# Layout.net
KiCad netlist of a schematic drawn in EAGLE
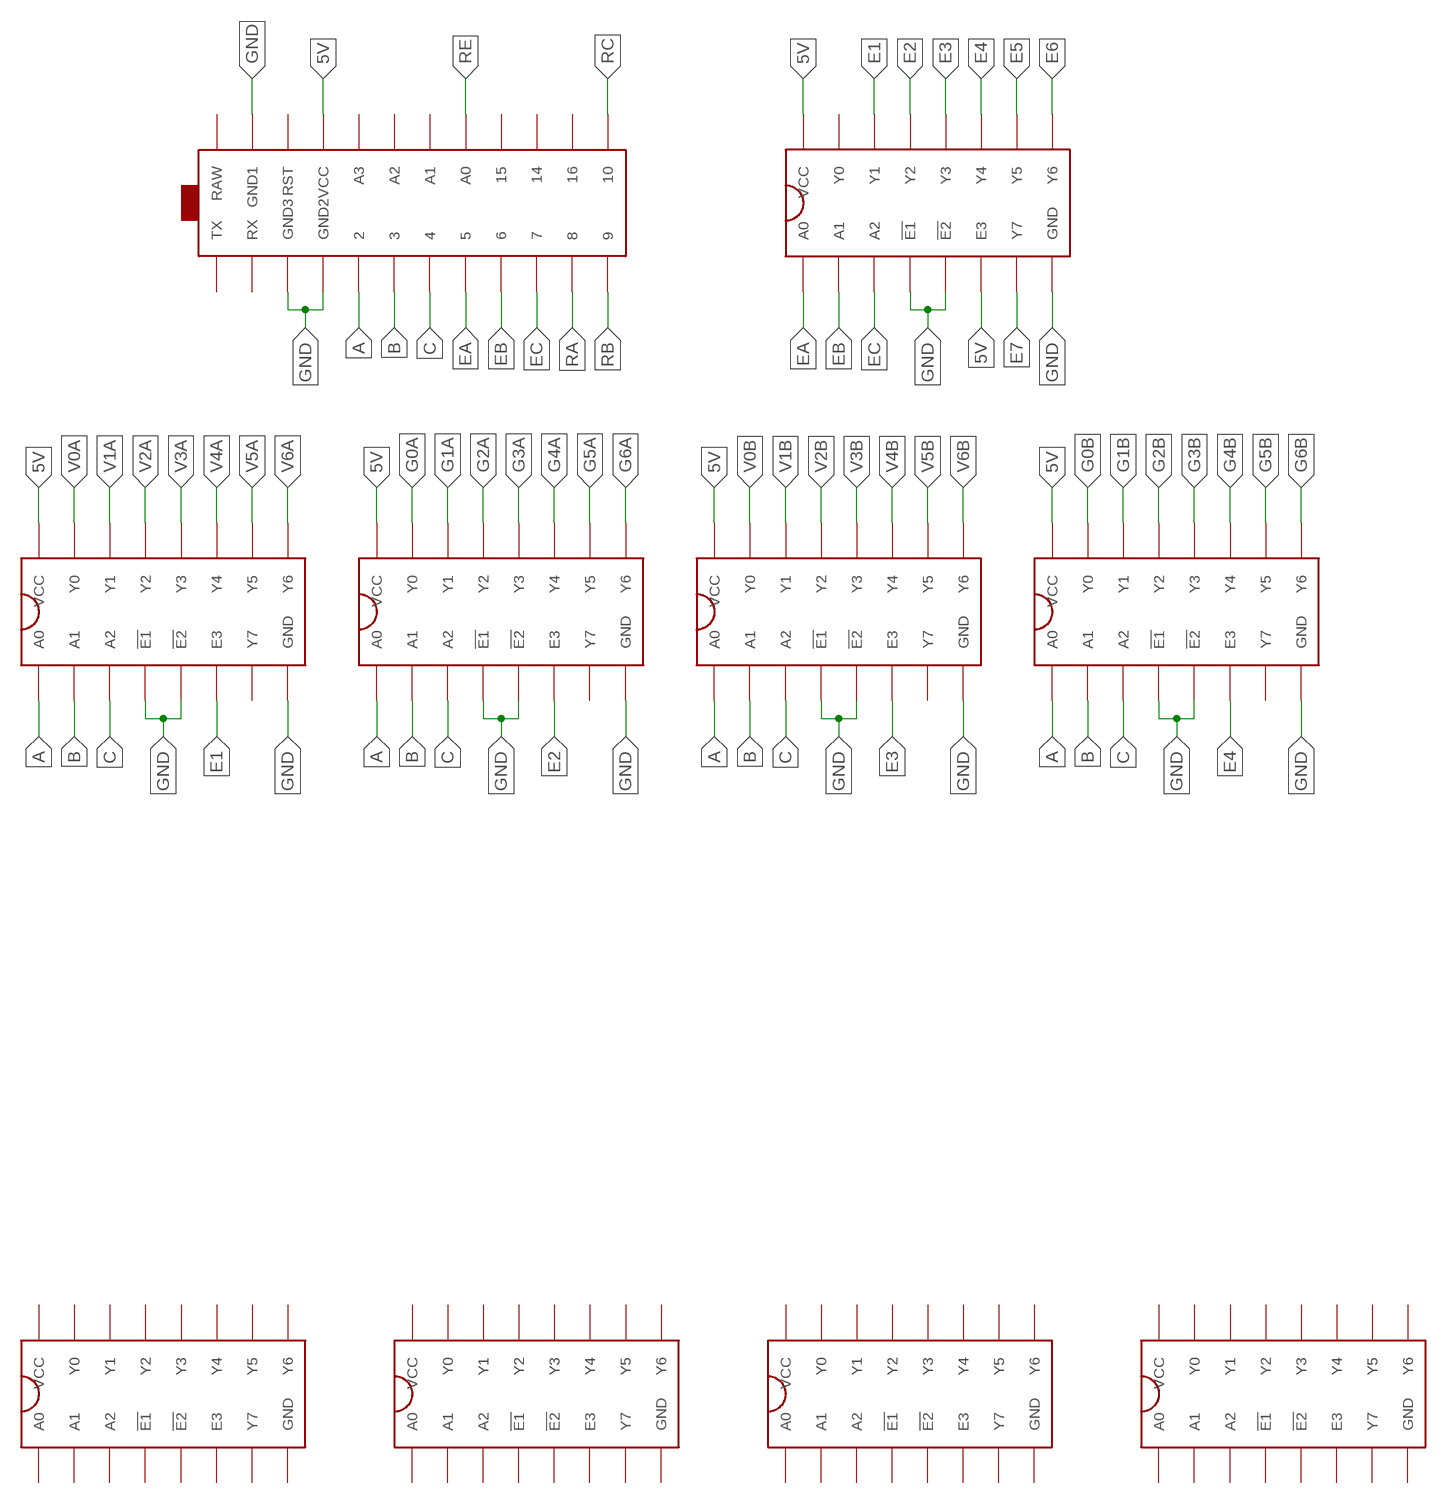
[diagram p0: schematic, sheet 1]

(export (version "E")
  (design (tool "Eeschema 10.0.6"))
  (components
    (comp (ref "U$1")
      (value "MCU")
      (footprint "eagle-import:MCU")
      (libsource (lib "eagle-import") (part "MCU"))
    )
    (comp (ref "U$2")
      (value "DEMUX")
      (footprint "eagle-import:DEMUX")
      (libsource (lib "eagle-import") (part "DEMUX"))
    )
    (comp (ref "U$3")
      (value "DEMUX")
      (footprint "eagle-import:DEMUX")
      (libsource (lib "eagle-import") (part "DEMUX"))
    )
    (comp (ref "U$4")
      (value "DEMUX")
      (footprint "eagle-import:DEMUX")
      (libsource (lib "eagle-import") (part "DEMUX"))
    )
    (comp (ref "U$5")
      (value "DEMUX")
      (footprint "eagle-import:DEMUX")
      (libsource (lib "eagle-import") (part "DEMUX"))
    )
    (comp (ref "U$6")
      (value "DEMUX")
      (footprint "eagle-import:DEMUX")
      (libsource (lib "eagle-import") (part "DEMUX"))
    )
    (comp (ref "U$7")
      (value "DEMUX")
      (footprint "eagle-import:DEMUX")
      (libsource (lib "eagle-import") (part "DEMUX"))
    )
    (comp (ref "U$8")
      (value "DEMUX")
      (footprint "eagle-import:DEMUX")
      (libsource (lib "eagle-import") (part "DEMUX"))
    )
    (comp (ref "U$9")
      (value "DEMUX")
      (footprint "eagle-import:DEMUX")
      (libsource (lib "eagle-import") (part "DEMUX"))
    )
    (comp (ref "U$10")
      (value "DEMUX")
      (footprint "eagle-import:DEMUX")
      (libsource (lib "eagle-import") (part "DEMUX"))
    )
  )
  (nets
    (net (code "1") (name "5V") (class "Default")
      (node (ref "U$1") (pin "P$24") (pinfunction "VCC_P$24") (pintype "bidirectional"))
      (node (ref "U$2") (pin "P$6") (pinfunction "E3_P$6") (pintype "bidirectional"))
      (node (ref "U$2") (pin "P$8") (pinfunction "VCC_P$8") (pintype "bidirectional"))
      (node (ref "U$3") (pin "P$8") (pinfunction "VCC_P$8") (pintype "bidirectional"))
      (node (ref "U$4") (pin "P$8") (pinfunction "VCC_P$8") (pintype "bidirectional"))
      (node (ref "U$5") (pin "P$8") (pinfunction "VCC_P$8") (pintype "bidirectional"))
      (node (ref "U$6") (pin "P$8") (pinfunction "VCC_P$8") (pintype "bidirectional"))
    )
    (net (code "2") (name "A") (class "Default")
      (node (ref "U$1") (pin "P$1") (pinfunction "2_P$1") (pintype "bidirectional"))
      (node (ref "U$3") (pin "P$3") (pinfunction "A0_P$3") (pintype "bidirectional"))
      (node (ref "U$4") (pin "P$3") (pinfunction "A0_P$3") (pintype "bidirectional"))
      (node (ref "U$5") (pin "P$3") (pinfunction "A0_P$3") (pintype "bidirectional"))
      (node (ref "U$6") (pin "P$3") (pinfunction "A0_P$3") (pintype "bidirectional"))
    )
    (net (code "3") (name "B") (class "Default")
      (node (ref "U$1") (pin "P$2") (pinfunction "3_P$2") (pintype "bidirectional"))
      (node (ref "U$3") (pin "P$4") (pinfunction "A1_P$4") (pintype "bidirectional"))
      (node (ref "U$4") (pin "P$4") (pinfunction "A1_P$4") (pintype "bidirectional"))
      (node (ref "U$5") (pin "P$4") (pinfunction "A1_P$4") (pintype "bidirectional"))
      (node (ref "U$6") (pin "P$4") (pinfunction "A1_P$4") (pintype "bidirectional"))
    )
    (net (code "4") (name "C") (class "Default")
      (node (ref "U$1") (pin "P$3") (pinfunction "4_P$3") (pintype "bidirectional"))
      (node (ref "U$3") (pin "P$5") (pinfunction "A2_P$5") (pintype "bidirectional"))
      (node (ref "U$4") (pin "P$5") (pinfunction "A2_P$5") (pintype "bidirectional"))
      (node (ref "U$5") (pin "P$5") (pinfunction "A2_P$5") (pintype "bidirectional"))
      (node (ref "U$6") (pin "P$5") (pinfunction "A2_P$5") (pintype "bidirectional"))
    )
    (net (code "5") (name "E1") (class "Default")
      (node (ref "U$2") (pin "P$10") (pinfunction "Y1_P$10") (pintype "bidirectional"))
      (node (ref "U$3") (pin "P$6") (pinfunction "E3_P$6") (pintype "bidirectional"))
    )
    (net (code "6") (name "E2") (class "Default")
      (node (ref "U$2") (pin "P$11") (pinfunction "Y2_P$11") (pintype "bidirectional"))
      (node (ref "U$4") (pin "P$6") (pinfunction "E3_P$6") (pintype "bidirectional"))
    )
    (net (code "7") (name "E3") (class "Default")
      (node (ref "U$2") (pin "P$12") (pinfunction "Y3_P$12") (pintype "bidirectional"))
      (node (ref "U$5") (pin "P$6") (pinfunction "E3_P$6") (pintype "bidirectional"))
    )
    (net (code "8") (name "E4") (class "Default")
      (node (ref "U$2") (pin "P$13") (pinfunction "Y4_P$13") (pintype "bidirectional"))
      (node (ref "U$6") (pin "P$6") (pinfunction "E3_P$6") (pintype "bidirectional"))
    )
    (net (code "9") (name "E5") (class "Default")
      (node (ref "U$2") (pin "P$14") (pinfunction "Y5_P$14") (pintype "bidirectional"))
    )
    (net (code "10") (name "E6") (class "Default")
      (node (ref "U$2") (pin "P$15") (pinfunction "Y6_P$15") (pintype "bidirectional"))
    )
    (net (code "11") (name "E7") (class "Default")
      (node (ref "U$2") (pin "P$16") (pinfunction "Y7_P$16") (pintype "bidirectional"))
    )
    (net (code "12") (name "EA") (class "Default")
      (node (ref "U$1") (pin "P$4") (pinfunction "5_P$4") (pintype "bidirectional"))
      (node (ref "U$2") (pin "P$3") (pinfunction "A0_P$3") (pintype "bidirectional"))
    )
    (net (code "13") (name "EB") (class "Default")
      (node (ref "U$1") (pin "P$5") (pinfunction "6_P$5") (pintype "bidirectional"))
      (node (ref "U$2") (pin "P$4") (pinfunction "A1_P$4") (pintype "bidirectional"))
    )
    (net (code "14") (name "EC") (class "Default")
      (node (ref "U$1") (pin "P$6") (pinfunction "7_P$6") (pintype "bidirectional"))
      (node (ref "U$2") (pin "P$5") (pinfunction "A2_P$5") (pintype "bidirectional"))
    )
    (net (code "15") (name "G0A") (class "Default")
      (node (ref "U$4") (pin "P$9") (pinfunction "Y0_P$9") (pintype "bidirectional"))
    )
    (net (code "16") (name "G0B") (class "Default")
      (node (ref "U$6") (pin "P$9") (pinfunction "Y0_P$9") (pintype "bidirectional"))
    )
    (net (code "17") (name "G1A") (class "Default")
      (node (ref "U$4") (pin "P$10") (pinfunction "Y1_P$10") (pintype "bidirectional"))
    )
    (net (code "18") (name "G1B") (class "Default")
      (node (ref "U$6") (pin "P$10") (pinfunction "Y1_P$10") (pintype "bidirectional"))
    )
    (net (code "19") (name "G2A") (class "Default")
      (node (ref "U$4") (pin "P$11") (pinfunction "Y2_P$11") (pintype "bidirectional"))
    )
    (net (code "20") (name "G2B") (class "Default")
      (node (ref "U$6") (pin "P$11") (pinfunction "Y2_P$11") (pintype "bidirectional"))
    )
    (net (code "21") (name "G3A") (class "Default")
      (node (ref "U$4") (pin "P$12") (pinfunction "Y3_P$12") (pintype "bidirectional"))
    )
    (net (code "22") (name "G3B") (class "Default")
      (node (ref "U$6") (pin "P$12") (pinfunction "Y3_P$12") (pintype "bidirectional"))
    )
    (net (code "23") (name "G4A") (class "Default")
      (node (ref "U$4") (pin "P$13") (pinfunction "Y4_P$13") (pintype "bidirectional"))
    )
    (net (code "24") (name "G4B") (class "Default")
      (node (ref "U$6") (pin "P$13") (pinfunction "Y4_P$13") (pintype "bidirectional"))
    )
    (net (code "25") (name "G5A") (class "Default")
      (node (ref "U$4") (pin "P$14") (pinfunction "Y5_P$14") (pintype "bidirectional"))
    )
    (net (code "26") (name "G5B") (class "Default")
      (node (ref "U$6") (pin "P$14") (pinfunction "Y5_P$14") (pintype "bidirectional"))
    )
    (net (code "27") (name "G6A") (class "Default")
      (node (ref "U$4") (pin "P$15") (pinfunction "Y6_P$15") (pintype "bidirectional"))
    )
    (net (code "28") (name "G6B") (class "Default")
      (node (ref "U$6") (pin "P$15") (pinfunction "Y6_P$15") (pintype "bidirectional"))
    )
    (net (code "29") (name "GND") (class "Default")
      (node (ref "U$1") (pin "P$17") (pinfunction "GND1_P$17") (pintype "bidirectional"))
      (node (ref "U$1") (pin "P$18") (pinfunction "GND2_P$18") (pintype "bidirectional"))
      (node (ref "U$1") (pin "P$19") (pinfunction "GND3_P$19") (pintype "bidirectional"))
      (node (ref "U$2") (pin "P$1") (pinfunction "~{E1}_P$1") (pintype "bidirectional"))
      (node (ref "U$2") (pin "P$2") (pinfunction "~{E2}_P$2") (pintype "bidirectional"))
      (node (ref "U$2") (pin "P$7") (pinfunction "GND_P$7") (pintype "bidirectional"))
      (node (ref "U$3") (pin "P$1") (pinfunction "~{E1}_P$1") (pintype "bidirectional"))
      (node (ref "U$3") (pin "P$2") (pinfunction "~{E2}_P$2") (pintype "bidirectional"))
      (node (ref "U$3") (pin "P$7") (pinfunction "GND_P$7") (pintype "bidirectional"))
      (node (ref "U$4") (pin "P$1") (pinfunction "~{E1}_P$1") (pintype "bidirectional"))
      (node (ref "U$4") (pin "P$2") (pinfunction "~{E2}_P$2") (pintype "bidirectional"))
      (node (ref "U$4") (pin "P$7") (pinfunction "GND_P$7") (pintype "bidirectional"))
      (node (ref "U$5") (pin "P$1") (pinfunction "~{E1}_P$1") (pintype "bidirectional"))
      (node (ref "U$5") (pin "P$2") (pinfunction "~{E2}_P$2") (pintype "bidirectional"))
      (node (ref "U$5") (pin "P$7") (pinfunction "GND_P$7") (pintype "bidirectional"))
      (node (ref "U$6") (pin "P$1") (pinfunction "~{E1}_P$1") (pintype "bidirectional"))
      (node (ref "U$6") (pin "P$2") (pinfunction "~{E2}_P$2") (pintype "bidirectional"))
      (node (ref "U$6") (pin "P$7") (pinfunction "GND_P$7") (pintype "bidirectional"))
    )
    (net (code "30") (name "RA") (class "Default")
      (node (ref "U$1") (pin "P$7") (pinfunction "8_P$7") (pintype "bidirectional"))
    )
    (net (code "31") (name "RB") (class "Default")
      (node (ref "U$1") (pin "P$8") (pinfunction "9_P$8") (pintype "bidirectional"))
    )
    (net (code "32") (name "RC") (class "Default")
      (node (ref "U$1") (pin "P$9") (pinfunction "10_P$9") (pintype "bidirectional"))
    )
    (net (code "33") (name "RE") (class "Default")
      (node (ref "U$1") (pin "P$13") (pinfunction "A0_P$13") (pintype "bidirectional"))
    )
    (net (code "34") (name "V0A") (class "Default")
      (node (ref "U$3") (pin "P$9") (pinfunction "Y0_P$9") (pintype "bidirectional"))
    )
    (net (code "35") (name "V0B") (class "Default")
      (node (ref "U$5") (pin "P$9") (pinfunction "Y0_P$9") (pintype "bidirectional"))
    )
    (net (code "36") (name "V1A") (class "Default")
      (node (ref "U$3") (pin "P$10") (pinfunction "Y1_P$10") (pintype "bidirectional"))
    )
    (net (code "37") (name "V1B") (class "Default")
      (node (ref "U$5") (pin "P$10") (pinfunction "Y1_P$10") (pintype "bidirectional"))
    )
    (net (code "38") (name "V2A") (class "Default")
      (node (ref "U$3") (pin "P$11") (pinfunction "Y2_P$11") (pintype "bidirectional"))
    )
    (net (code "39") (name "V2B") (class "Default")
      (node (ref "U$5") (pin "P$11") (pinfunction "Y2_P$11") (pintype "bidirectional"))
    )
    (net (code "40") (name "V3A") (class "Default")
      (node (ref "U$3") (pin "P$12") (pinfunction "Y3_P$12") (pintype "bidirectional"))
    )
    (net (code "41") (name "V3B") (class "Default")
      (node (ref "U$5") (pin "P$12") (pinfunction "Y3_P$12") (pintype "bidirectional"))
    )
    (net (code "42") (name "V4A") (class "Default")
      (node (ref "U$3") (pin "P$13") (pinfunction "Y4_P$13") (pintype "bidirectional"))
    )
    (net (code "43") (name "V4B") (class "Default")
      (node (ref "U$5") (pin "P$13") (pinfunction "Y4_P$13") (pintype "bidirectional"))
    )
    (net (code "44") (name "V5A") (class "Default")
      (node (ref "U$3") (pin "P$14") (pinfunction "Y5_P$14") (pintype "bidirectional"))
    )
    (net (code "45") (name "V5B") (class "Default")
      (node (ref "U$5") (pin "P$14") (pinfunction "Y5_P$14") (pintype "bidirectional"))
    )
    (net (code "46") (name "V6A") (class "Default")
      (node (ref "U$3") (pin "P$15") (pinfunction "Y6_P$15") (pintype "bidirectional"))
    )
    (net (code "47") (name "V6B") (class "Default")
      (node (ref "U$5") (pin "P$15") (pinfunction "Y6_P$15") (pintype "bidirectional"))
    )
    (net (code "48") (name "unconnected-(U$1-14-PadP$10)") (class "Default")
      (node (ref "U$1") (pin "P$10") (pinfunction "14_P$10") (pintype "bidirectional"))
    )
    (net (code "49") (name "unconnected-(U$1-15-PadP$11)") (class "Default")
      (node (ref "U$1") (pin "P$11") (pinfunction "15_P$11") (pintype "bidirectional"))
    )
    (net (code "50") (name "unconnected-(U$1-16-PadP$12)") (class "Default")
      (node (ref "U$1") (pin "P$12") (pinfunction "16_P$12") (pintype "bidirectional"))
    )
    (net (code "51") (name "unconnected-(U$1-A1-PadP$14)") (class "Default")
      (node (ref "U$1") (pin "P$14") (pinfunction "A1_P$14") (pintype "bidirectional"))
    )
    (net (code "52") (name "unconnected-(U$1-A2-PadP$15)") (class "Default")
      (node (ref "U$1") (pin "P$15") (pinfunction "A2_P$15") (pintype "bidirectional"))
    )
    (net (code "53") (name "unconnected-(U$1-A3-PadP$16)") (class "Default")
      (node (ref "U$1") (pin "P$16") (pinfunction "A3_P$16") (pintype "bidirectional"))
    )
    (net (code "54") (name "unconnected-(U$1-RAW-PadP$20)") (class "Default")
      (node (ref "U$1") (pin "P$20") (pinfunction "RAW_P$20") (pintype "bidirectional"))
    )
    (net (code "55") (name "unconnected-(U$1-RST-PadP$21)") (class "Default")
      (node (ref "U$1") (pin "P$21") (pinfunction "RST_P$21") (pintype "bidirectional"))
    )
    (net (code "56") (name "unconnected-(U$1-RX-PadP$22)") (class "Default")
      (node (ref "U$1") (pin "P$22") (pinfunction "RX_P$22") (pintype "bidirectional"))
    )
    (net (code "57") (name "unconnected-(U$1-TX-PadP$23)") (class "Default")
      (node (ref "U$1") (pin "P$23") (pinfunction "TX_P$23") (pintype "bidirectional"))
    )
    (net (code "58") (name "unconnected-(U$2-Y0-PadP$9)") (class "Default")
      (node (ref "U$2") (pin "P$9") (pinfunction "Y0_P$9") (pintype "bidirectional"))
    )
    (net (code "59") (name "unconnected-(U$3-Y7-PadP$16)") (class "Default")
      (node (ref "U$3") (pin "P$16") (pinfunction "Y7_P$16") (pintype "bidirectional"))
    )
    (net (code "60") (name "unconnected-(U$4-Y7-PadP$16)") (class "Default")
      (node (ref "U$4") (pin "P$16") (pinfunction "Y7_P$16") (pintype "bidirectional"))
    )
    (net (code "61") (name "unconnected-(U$5-Y7-PadP$16)") (class "Default")
      (node (ref "U$5") (pin "P$16") (pinfunction "Y7_P$16") (pintype "bidirectional"))
    )
    (net (code "62") (name "unconnected-(U$6-Y7-PadP$16)") (class "Default")
      (node (ref "U$6") (pin "P$16") (pinfunction "Y7_P$16") (pintype "bidirectional"))
    )
    (net (code "63") (name "unconnected-(U$7-A0-PadP$3)") (class "Default")
      (node (ref "U$7") (pin "P$3") (pinfunction "A0_P$3") (pintype "bidirectional"))
    )
    (net (code "64") (name "unconnected-(U$7-A1-PadP$4)") (class "Default")
      (node (ref "U$7") (pin "P$4") (pinfunction "A1_P$4") (pintype "bidirectional"))
    )
    (net (code "65") (name "unconnected-(U$7-A2-PadP$5)") (class "Default")
      (node (ref "U$7") (pin "P$5") (pinfunction "A2_P$5") (pintype "bidirectional"))
    )
    (net (code "66") (name "unconnected-(U$7-E3-PadP$6)") (class "Default")
      (node (ref "U$7") (pin "P$6") (pinfunction "E3_P$6") (pintype "bidirectional"))
    )
    (net (code "67") (name "unconnected-(U$7-GND-PadP$7)") (class "Default")
      (node (ref "U$7") (pin "P$7") (pinfunction "GND_P$7") (pintype "bidirectional"))
    )
    (net (code "68") (name "unconnected-(U$7-VCC-PadP$8)") (class "Default")
      (node (ref "U$7") (pin "P$8") (pinfunction "VCC_P$8") (pintype "bidirectional"))
    )
    (net (code "69") (name "unconnected-(U$7-Y0-PadP$9)") (class "Default")
      (node (ref "U$7") (pin "P$9") (pinfunction "Y0_P$9") (pintype "bidirectional"))
    )
    (net (code "70") (name "unconnected-(U$7-Y1-PadP$10)") (class "Default")
      (node (ref "U$7") (pin "P$10") (pinfunction "Y1_P$10") (pintype "bidirectional"))
    )
    (net (code "71") (name "unconnected-(U$7-Y2-PadP$11)") (class "Default")
      (node (ref "U$7") (pin "P$11") (pinfunction "Y2_P$11") (pintype "bidirectional"))
    )
    (net (code "72") (name "unconnected-(U$7-Y3-PadP$12)") (class "Default")
      (node (ref "U$7") (pin "P$12") (pinfunction "Y3_P$12") (pintype "bidirectional"))
    )
    (net (code "73") (name "unconnected-(U$7-Y4-PadP$13)") (class "Default")
      (node (ref "U$7") (pin "P$13") (pinfunction "Y4_P$13") (pintype "bidirectional"))
    )
    (net (code "74") (name "unconnected-(U$7-Y5-PadP$14)") (class "Default")
      (node (ref "U$7") (pin "P$14") (pinfunction "Y5_P$14") (pintype "bidirectional"))
    )
    (net (code "75") (name "unconnected-(U$7-Y6-PadP$15)") (class "Default")
      (node (ref "U$7") (pin "P$15") (pinfunction "Y6_P$15") (pintype "bidirectional"))
    )
    (net (code "76") (name "unconnected-(U$7-Y7-PadP$16)") (class "Default")
      (node (ref "U$7") (pin "P$16") (pinfunction "Y7_P$16") (pintype "bidirectional"))
    )
    (net (code "77") (name "unconnected-(U$7-~{E1}-PadP$1)") (class "Default")
      (node (ref "U$7") (pin "P$1") (pinfunction "~{E1}_P$1") (pintype "bidirectional"))
    )
    (net (code "78") (name "unconnected-(U$7-~{E2}-PadP$2)") (class "Default")
      (node (ref "U$7") (pin "P$2") (pinfunction "~{E2}_P$2") (pintype "bidirectional"))
    )
    (net (code "79") (name "unconnected-(U$8-A0-PadP$3)") (class "Default")
      (node (ref "U$8") (pin "P$3") (pinfunction "A0_P$3") (pintype "bidirectional"))
    )
    (net (code "80") (name "unconnected-(U$8-A1-PadP$4)") (class "Default")
      (node (ref "U$8") (pin "P$4") (pinfunction "A1_P$4") (pintype "bidirectional"))
    )
    (net (code "81") (name "unconnected-(U$8-A2-PadP$5)") (class "Default")
      (node (ref "U$8") (pin "P$5") (pinfunction "A2_P$5") (pintype "bidirectional"))
    )
    (net (code "82") (name "unconnected-(U$8-E3-PadP$6)") (class "Default")
      (node (ref "U$8") (pin "P$6") (pinfunction "E3_P$6") (pintype "bidirectional"))
    )
    (net (code "83") (name "unconnected-(U$8-GND-PadP$7)") (class "Default")
      (node (ref "U$8") (pin "P$7") (pinfunction "GND_P$7") (pintype "bidirectional"))
    )
    (net (code "84") (name "unconnected-(U$8-VCC-PadP$8)") (class "Default")
      (node (ref "U$8") (pin "P$8") (pinfunction "VCC_P$8") (pintype "bidirectional"))
    )
    (net (code "85") (name "unconnected-(U$8-Y0-PadP$9)") (class "Default")
      (node (ref "U$8") (pin "P$9") (pinfunction "Y0_P$9") (pintype "bidirectional"))
    )
    (net (code "86") (name "unconnected-(U$8-Y1-PadP$10)") (class "Default")
      (node (ref "U$8") (pin "P$10") (pinfunction "Y1_P$10") (pintype "bidirectional"))
    )
    (net (code "87") (name "unconnected-(U$8-Y2-PadP$11)") (class "Default")
      (node (ref "U$8") (pin "P$11") (pinfunction "Y2_P$11") (pintype "bidirectional"))
    )
    (net (code "88") (name "unconnected-(U$8-Y3-PadP$12)") (class "Default")
      (node (ref "U$8") (pin "P$12") (pinfunction "Y3_P$12") (pintype "bidirectional"))
    )
    (net (code "89") (name "unconnected-(U$8-Y4-PadP$13)") (class "Default")
      (node (ref "U$8") (pin "P$13") (pinfunction "Y4_P$13") (pintype "bidirectional"))
    )
    (net (code "90") (name "unconnected-(U$8-Y5-PadP$14)") (class "Default")
      (node (ref "U$8") (pin "P$14") (pinfunction "Y5_P$14") (pintype "bidirectional"))
    )
    (net (code "91") (name "unconnected-(U$8-Y6-PadP$15)") (class "Default")
      (node (ref "U$8") (pin "P$15") (pinfunction "Y6_P$15") (pintype "bidirectional"))
    )
    (net (code "92") (name "unconnected-(U$8-Y7-PadP$16)") (class "Default")
      (node (ref "U$8") (pin "P$16") (pinfunction "Y7_P$16") (pintype "bidirectional"))
    )
    (net (code "93") (name "unconnected-(U$8-~{E1}-PadP$1)") (class "Default")
      (node (ref "U$8") (pin "P$1") (pinfunction "~{E1}_P$1") (pintype "bidirectional"))
    )
    (net (code "94") (name "unconnected-(U$8-~{E2}-PadP$2)") (class "Default")
      (node (ref "U$8") (pin "P$2") (pinfunction "~{E2}_P$2") (pintype "bidirectional"))
    )
    (net (code "95") (name "unconnected-(U$9-A0-PadP$3)") (class "Default")
      (node (ref "U$9") (pin "P$3") (pinfunction "A0_P$3") (pintype "bidirectional"))
    )
    (net (code "96") (name "unconnected-(U$9-A1-PadP$4)") (class "Default")
      (node (ref "U$9") (pin "P$4") (pinfunction "A1_P$4") (pintype "bidirectional"))
    )
    (net (code "97") (name "unconnected-(U$9-A2-PadP$5)") (class "Default")
      (node (ref "U$9") (pin "P$5") (pinfunction "A2_P$5") (pintype "bidirectional"))
    )
    (net (code "98") (name "unconnected-(U$9-E3-PadP$6)") (class "Default")
      (node (ref "U$9") (pin "P$6") (pinfunction "E3_P$6") (pintype "bidirectional"))
    )
    (net (code "99") (name "unconnected-(U$9-GND-PadP$7)") (class "Default")
      (node (ref "U$9") (pin "P$7") (pinfunction "GND_P$7") (pintype "bidirectional"))
    )
    (net (code "100") (name "unconnected-(U$9-VCC-PadP$8)") (class "Default")
      (node (ref "U$9") (pin "P$8") (pinfunction "VCC_P$8") (pintype "bidirectional"))
    )
    (net (code "101") (name "unconnected-(U$9-Y0-PadP$9)") (class "Default")
      (node (ref "U$9") (pin "P$9") (pinfunction "Y0_P$9") (pintype "bidirectional"))
    )
    (net (code "102") (name "unconnected-(U$9-Y1-PadP$10)") (class "Default")
      (node (ref "U$9") (pin "P$10") (pinfunction "Y1_P$10") (pintype "bidirectional"))
    )
    (net (code "103") (name "unconnected-(U$9-Y2-PadP$11)") (class "Default")
      (node (ref "U$9") (pin "P$11") (pinfunction "Y2_P$11") (pintype "bidirectional"))
    )
    (net (code "104") (name "unconnected-(U$9-Y3-PadP$12)") (class "Default")
      (node (ref "U$9") (pin "P$12") (pinfunction "Y3_P$12") (pintype "bidirectional"))
    )
    (net (code "105") (name "unconnected-(U$9-Y4-PadP$13)") (class "Default")
      (node (ref "U$9") (pin "P$13") (pinfunction "Y4_P$13") (pintype "bidirectional"))
    )
    (net (code "106") (name "unconnected-(U$9-Y5-PadP$14)") (class "Default")
      (node (ref "U$9") (pin "P$14") (pinfunction "Y5_P$14") (pintype "bidirectional"))
    )
    (net (code "107") (name "unconnected-(U$9-Y6-PadP$15)") (class "Default")
      (node (ref "U$9") (pin "P$15") (pinfunction "Y6_P$15") (pintype "bidirectional"))
    )
    (net (code "108") (name "unconnected-(U$9-Y7-PadP$16)") (class "Default")
      (node (ref "U$9") (pin "P$16") (pinfunction "Y7_P$16") (pintype "bidirectional"))
    )
    (net (code "109") (name "unconnected-(U$9-~{E1}-PadP$1)") (class "Default")
      (node (ref "U$9") (pin "P$1") (pinfunction "~{E1}_P$1") (pintype "bidirectional"))
    )
    (net (code "110") (name "unconnected-(U$9-~{E2}-PadP$2)") (class "Default")
      (node (ref "U$9") (pin "P$2") (pinfunction "~{E2}_P$2") (pintype "bidirectional"))
    )
    (net (code "111") (name "unconnected-(U$10-A0-PadP$3)") (class "Default")
      (node (ref "U$10") (pin "P$3") (pinfunction "A0_P$3") (pintype "bidirectional"))
    )
    (net (code "112") (name "unconnected-(U$10-A1-PadP$4)") (class "Default")
      (node (ref "U$10") (pin "P$4") (pinfunction "A1_P$4") (pintype "bidirectional"))
    )
    (net (code "113") (name "unconnected-(U$10-A2-PadP$5)") (class "Default")
      (node (ref "U$10") (pin "P$5") (pinfunction "A2_P$5") (pintype "bidirectional"))
    )
    (net (code "114") (name "unconnected-(U$10-E3-PadP$6)") (class "Default")
      (node (ref "U$10") (pin "P$6") (pinfunction "E3_P$6") (pintype "bidirectional"))
    )
    (net (code "115") (name "unconnected-(U$10-GND-PadP$7)") (class "Default")
      (node (ref "U$10") (pin "P$7") (pinfunction "GND_P$7") (pintype "bidirectional"))
    )
    (net (code "116") (name "unconnected-(U$10-VCC-PadP$8)") (class "Default")
      (node (ref "U$10") (pin "P$8") (pinfunction "VCC_P$8") (pintype "bidirectional"))
    )
    (net (code "117") (name "unconnected-(U$10-Y0-PadP$9)") (class "Default")
      (node (ref "U$10") (pin "P$9") (pinfunction "Y0_P$9") (pintype "bidirectional"))
    )
    (net (code "118") (name "unconnected-(U$10-Y1-PadP$10)") (class "Default")
      (node (ref "U$10") (pin "P$10") (pinfunction "Y1_P$10") (pintype "bidirectional"))
    )
    (net (code "119") (name "unconnected-(U$10-Y2-PadP$11)") (class "Default")
      (node (ref "U$10") (pin "P$11") (pinfunction "Y2_P$11") (pintype "bidirectional"))
    )
    (net (code "120") (name "unconnected-(U$10-Y3-PadP$12)") (class "Default")
      (node (ref "U$10") (pin "P$12") (pinfunction "Y3_P$12") (pintype "bidirectional"))
    )
    (net (code "121") (name "unconnected-(U$10-Y4-PadP$13)") (class "Default")
      (node (ref "U$10") (pin "P$13") (pinfunction "Y4_P$13") (pintype "bidirectional"))
    )
    (net (code "122") (name "unconnected-(U$10-Y5-PadP$14)") (class "Default")
      (node (ref "U$10") (pin "P$14") (pinfunction "Y5_P$14") (pintype "bidirectional"))
    )
    (net (code "123") (name "unconnected-(U$10-Y6-PadP$15)") (class "Default")
      (node (ref "U$10") (pin "P$15") (pinfunction "Y6_P$15") (pintype "bidirectional"))
    )
    (net (code "124") (name "unconnected-(U$10-Y7-PadP$16)") (class "Default")
      (node (ref "U$10") (pin "P$16") (pinfunction "Y7_P$16") (pintype "bidirectional"))
    )
    (net (code "125") (name "unconnected-(U$10-~{E1}-PadP$1)") (class "Default")
      (node (ref "U$10") (pin "P$1") (pinfunction "~{E1}_P$1") (pintype "bidirectional"))
    )
    (net (code "126") (name "unconnected-(U$10-~{E2}-PadP$2)") (class "Default")
      (node (ref "U$10") (pin "P$2") (pinfunction "~{E2}_P$2") (pintype "bidirectional"))
    )
  )
)
